# SCH_MUSICA.net
KiCad netlist of a schematic drawn in EasyEDA
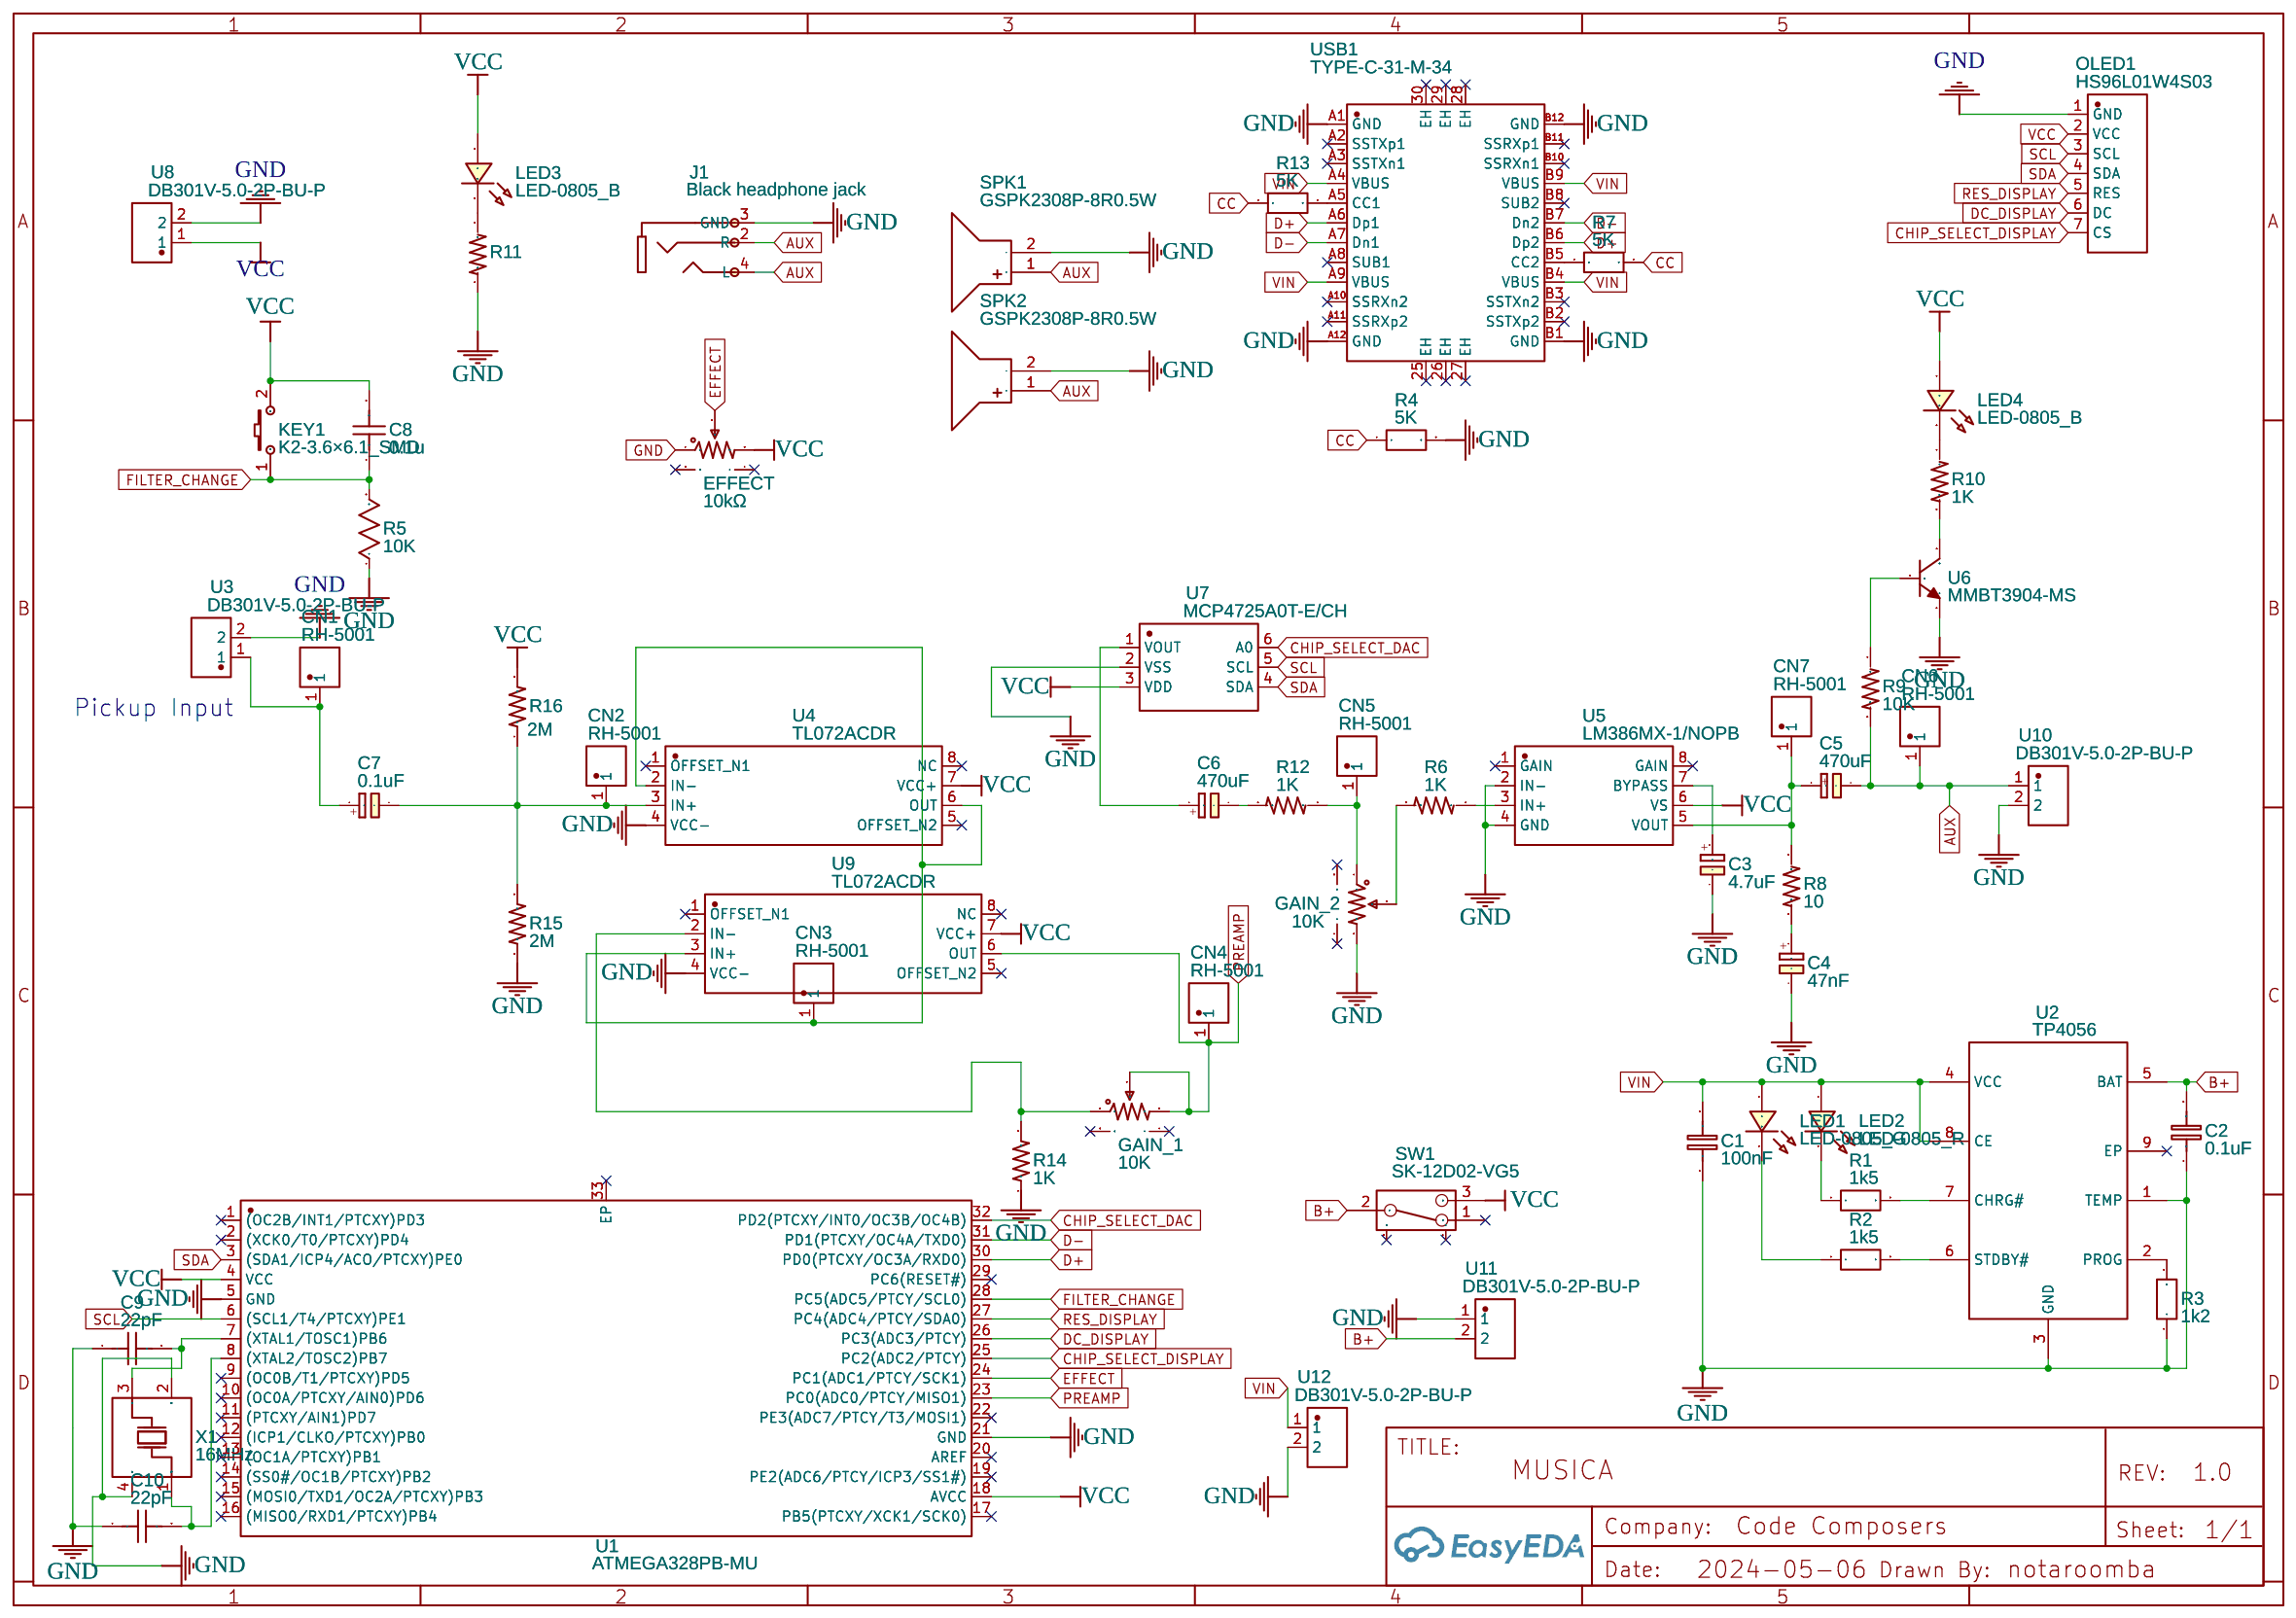
[diagram p0: schematic sheet]

(export (version "E")
  (design (tool "Eeschema 10.0.6"))
  (components
    (comp (ref "C1") (value "100nF") (libsource (lib "") (part "C_0603_EU")))
    (comp (ref "C2") (value "0.1uF") (libsource (lib "") (part "C_0603_EU")))
    (comp (ref "C3") (value "4.7uF") (libsource (lib "") (part "CAPACITOR_POL_S_1")))
    (comp (ref "C4") (value "47nF") (libsource (lib "") (part "CAPACITOR_POL_S_1")))
    (comp (ref "C5") (value "470uF") (libsource (lib "") (part "CAPACITOR_POL_S_2")))
    (comp (ref "C6") (value "470uF") (libsource (lib "") (part "CAPACITOR_POL_S")))
    (comp (ref "C7") (value "0.1uF") (libsource (lib "") (part "CAPACITOR_POL_S")))
    (comp (ref "C8") (value "0.1u") (libsource (lib "") (part "C_0603_US_1")))
    (comp (ref "C9") (value "22pF") (libsource (lib "") (part "C_0603_US")))
    (comp (ref "C10") (value "22pF") (libsource (lib "") (part "C_0603_US")))
    (comp (ref "CN1")
      (value "RH-5001")
      (fields (field (name "Manufacturer") "荣和"))
      (libsource (lib "") (part "RH-5001"))
    )
    (comp (ref "CN2")
      (value "RH-5001")
      (fields (field (name "Manufacturer") "荣和"))
      (libsource (lib "") (part "RH-5001"))
    )
    (comp (ref "CN3")
      (value "RH-5001")
      (fields (field (name "Manufacturer") "荣和"))
      (libsource (lib "") (part "RH-5001"))
    )
    (comp (ref "CN4")
      (value "RH-5001")
      (fields (field (name "Manufacturer") "荣和"))
      (libsource (lib "") (part "RH-5001"))
    )
    (comp (ref "CN5")
      (value "RH-5001")
      (fields (field (name "Manufacturer") "荣和"))
      (libsource (lib "") (part "RH-5001"))
    )
    (comp (ref "CN6")
      (value "RH-5001")
      (fields (field (name "Manufacturer") "荣和"))
      (libsource (lib "") (part "RH-5001"))
    )
    (comp (ref "CN7")
      (value "RH-5001")
      (fields (field (name "Manufacturer") "荣和"))
      (libsource (lib "") (part "RH-5001"))
    )
    (comp (ref "EFFECT")
      (value "10kΩ")
      (fields
        (field (name "Manufacturer Part") "RK09L114001T")
        (field (name "Manufacturer") "ALPSALPINE(阿尔卑斯阿尔派)")
      )
      (libsource (lib "") (part "RK09L114001T_2"))
    )
    (comp (ref "GAIN_1")
      (value "10K")
      (fields
        (field (name "Manufacturer Part") "RK09L114001T")
        (field (name "Manufacturer") "ALPSALPINE(阿尔卑斯阿尔派)")
      )
      (libsource (lib "") (part "RK09L114001T_1"))
    )
    (comp (ref "GAIN_2")
      (value "10K")
      (fields
        (field (name "Manufacturer Part") "RK09L114001T")
        (field (name "Manufacturer") "ALPSALPINE(阿尔卑斯阿尔派)")
      )
      (libsource (lib "") (part "RK09L114001T"))
    )
    (comp (ref "J1")
      (value "Black headphone jack")
      (fields (field (name "Manufacturer Part") "320B直插") (field (name "Manufacturer") "BOOMELE(博穆精密)"))
      (libsource (lib "") (part "Black headphone jack"))
    )
    (comp (ref "KEY1")
      (value "K2-3.6×6.1_SMD")
      (fields (field (name "Manufacturer Part") "K2-1107ST-A4SW-06"))
      (libsource (lib "") (part "K2-3.6×6.1_SMD"))
    )
    (comp (ref "LED1")
      (value "LED-0805_G")
      (fields (field (name "Manufacturer Part") "NCD0805G1") (field (name "Manufacturer") "国星光电"))
      (libsource (lib "") (part "LED-0805_G"))
    )
    (comp (ref "LED2")
      (value "LED-0805_R")
      (fields
        (field (name "Manufacturer Part") "17-21SURC/S530-A3/TR8")
        (field (name "Manufacturer") "EVERLIGHT(台湾亿光)")
      )
      (libsource (lib "") (part "LED-0805_R"))
    )
    (comp (ref "LED3")
      (value "LED-0805_B")
      (fields (field (name "Manufacturer Part") "D-B080508B1-KS2") (field (name "Manufacturer") "方舟 ARKLED"))
      (libsource (lib "") (part "LED-0805_B"))
    )
    (comp (ref "LED4")
      (value "LED-0805_B")
      (fields (field (name "Manufacturer Part") "D-B080508B1-KS2") (field (name "Manufacturer") "方舟 ARKLED"))
      (libsource (lib "") (part "LED-0805_B"))
    )
    (comp (ref "OLED1")
      (value "HS96L01W4S03")
      (fields (field (name "Manufacturer") "HS(汉昇)"))
      (libsource (lib "") (part "HS96L01W4S03"))
    )
    (comp (ref "R1") (value "1k5") (libsource (lib "") (part "R_0603_EU")))
    (comp (ref "R2") (value "1k5") (libsource (lib "") (part "R_0603_EU")))
    (comp (ref "R3") (value "1k2") (libsource (lib "") (part "R_0603_EU_1")))
    (comp (ref "R4") (value "5K") (libsource (lib "") (part "R_0603_EU")))
    (comp (ref "R5") (value "10K") (libsource (lib "") (part "R_0603_US")))
    (comp (ref "R6") (value "1K") (libsource (lib "") (part "RESISTOR0805-RES_2")))
    (comp (ref "R7") (value "5K") (libsource (lib "") (part "R_0603_EU")))
    (comp (ref "R8") (value "10") (libsource (lib "") (part "RESISTOR0805-RES_1")))
    (comp (ref "R9") (value "10K") (libsource (lib "") (part "RESISTOR0805-RES_1")))
    (comp (ref "R10") (value "1K") (libsource (lib "") (part "RESISTOR0805-RES_1")))
    (comp (ref "R11") (value "1K") (libsource (lib "") (part "RESISTOR0805-RES_1")))
    (comp (ref "R12") (value "1K") (libsource (lib "") (part "RESISTOR0805-RES_2")))
    (comp (ref "R13") (value "5K") (libsource (lib "") (part "R_0603_EU")))
    (comp (ref "R14") (value "1K") (libsource (lib "") (part "RESISTOR0805-RES")))
    (comp (ref "R15") (value "2M") (libsource (lib "") (part "RESISTOR0805-RES")))
    (comp (ref "R16") (value "2M") (libsource (lib "") (part "RESISTOR0805-RES")))
    (comp (ref "SPK1")
      (value "GSPK2308P-8R0.5W")
      (fields (field (name "Manufacturer") "INGHAi(赢海)"))
      (libsource (lib "") (part "GSPK2308P-8R0.5W"))
    )
    (comp (ref "SPK2")
      (value "GSPK2308P-8R0.5W")
      (fields (field (name "Manufacturer") "INGHAi(赢海)"))
      (libsource (lib "") (part "GSPK2308P-8R0.5W"))
    )
    (comp (ref "SW1")
      (value "SK-12D02-VG5")
      (fields (field (name "Manufacturer") "Rectangular Connectors - Contacts"))
      (libsource (lib "") (part "SK-12D02-VG5"))
    )
    (comp (ref "U1")
      (value "ATMEGA328PB-MU")
      (fields (field (name "Manufacturer") "MICROCHIP(美国微芯)"))
      (libsource (lib "") (part "ATMEGA328PB-MU"))
    )
    (comp (ref "U2")
      (value "TP4056")
      (fields
        (field (name "Manufacturer Part") "TP4056-42-ESOP8")
        (field (name "Manufacturer") "TOPPOWER(南京拓微)")
      )
      (libsource (lib "") (part "TP4056"))
    )
    (comp (ref "U3")
      (value "DB301V-5.0-2P-BU-P")
      (fields (field (name "Manufacturer") "DORABO(地博电气)"))
      (libsource (lib "") (part "DB301V-5.0-2P-BU-P"))
    )
    (comp (ref "U4")
      (value "TL072ACDR")
      (fields (field (name "Manufacturer") "TI(德州仪器)"))
      (libsource (lib "") (part "TL072ACDR"))
    )
    (comp (ref "U5")
      (value "LM386MX-1/NOPB")
      (fields (field (name "Manufacturer") "TI(德州仪器)"))
      (libsource (lib "") (part "LM386MX-1/NOPB"))
    )
    (comp (ref "U6")
      (value "MMBT3904-MS")
      (fields (field (name "Manufacturer") "MSKSEMI(美森科)"))
      (libsource (lib "") (part "MMBT3904-MS"))
    )
    (comp (ref "U7")
      (value "MCP4725A0T-E/CH")
      (fields (field (name "Manufacturer") "MICROCHIP(美国微芯)"))
      (libsource (lib "") (part "MCP4725A0T-E/CH"))
    )
    (comp (ref "U8")
      (value "DB301V-5.0-2P-BU-P")
      (fields (field (name "Manufacturer") "DORABO(地博电气)"))
      (libsource (lib "") (part "DB301V-5.0-2P-BU-P"))
    )
    (comp (ref "U9")
      (value "TL072ACDR")
      (fields (field (name "Manufacturer") "TI(德州仪器)"))
      (libsource (lib "") (part "TL072ACDR"))
    )
    (comp (ref "U10")
      (value "DB301V-5.0-2P-BU-P")
      (fields (field (name "Manufacturer") "DORABO(地博电气)"))
      (libsource (lib "") (part "DB301V-5.0-2P-BU-P_1"))
    )
    (comp (ref "U11")
      (value "DB301V-5.0-2P-BU-P")
      (fields (field (name "Manufacturer") "DORABO(地博电气)"))
      (libsource (lib "") (part "DB301V-5.0-2P-BU-P_1"))
    )
    (comp (ref "U12")
      (value "DB301V-5.0-2P-BU-P")
      (fields (field (name "Manufacturer") "DORABO(地博电气)"))
      (libsource (lib "") (part "DB301V-5.0-2P-BU-P_1"))
    )
    (comp (ref "USB1")
      (value "TYPE-C-31-M-34")
      (fields (field (name "Manufacturer") "韩国韩荣"))
      (libsource (lib "") (part "TYPE-C-31-M-34"))
    )
    (comp (ref "X1")
      (value "16MHz")
      (fields (field (name "Manufacturer Part") "X322516MLB4SI") (field (name "Manufacturer") "YXC(扬兴晶振)"))
      (libsource (lib "") (part "X322516MLB4SI"))
    )
  )
  (nets
    (net (code "1") (name "AUX") (class "Default")
      (node (ref "C5") (pin "-") (pinfunction "-_-") (pintype "unspecified"))
      (node (ref "CN6") (pin "1") (pinfunction "1_1") (pintype "unspecified"))
      (node (ref "J1") (pin "2") (pinfunction "R_2") (pintype "input"))
      (node (ref "J1") (pin "4") (pinfunction "L_4") (pintype "input"))
      (node (ref "R9") (pin "2") (pinfunction "2_2") (pintype "bidirectional"))
      (node (ref "SPK1") (pin "1") (pinfunction "+_1") (pintype "unspecified"))
      (node (ref "SPK2") (pin "1") (pinfunction "+_1") (pintype "unspecified"))
      (node (ref "U10") (pin "1") (pinfunction "1_1") (pintype "unspecified"))
    )
    (net (code "2") (name "B+") (class "Default")
      (node (ref "C2") (pin "2") (pinfunction "2_2") (pintype "unspecified"))
      (node (ref "SW1") (pin "2") (pinfunction "2_2") (pintype "unspecified"))
      (node (ref "U11") (pin "2") (pinfunction "2_2") (pintype "unspecified"))
      (node (ref "U2") (pin "5") (pinfunction "BAT_5") (pintype "unspecified"))
    )
    (net (code "3") (name "CC") (class "Default")
      (node (ref "R13") (pin "1") (pinfunction "1_1") (pintype "unspecified"))
      (node (ref "R4") (pin "1") (pinfunction "1_1") (pintype "unspecified"))
      (node (ref "R7") (pin "2") (pinfunction "2_2") (pintype "unspecified"))
    )
    (net (code "4") (name "CHIP_SELECT_DAC") (class "Default")
      (node (ref "U1") (pin "32") (pinfunction "PD2(PTCXY/INT0/OC3B/OC4B)_32") (pintype "unspecified"))
      (node (ref "U7") (pin "6") (pinfunction "A0_6") (pintype "unspecified"))
    )
    (net (code "5") (name "CHIP_SELECT_DISPLAY") (class "Default")
      (node (ref "OLED1") (pin "7") (pinfunction "CS_7") (pintype "unspecified"))
      (node (ref "U1") (pin "25") (pinfunction "PC2(ADC2/PTCY)_25") (pintype "unspecified"))
    )
    (net (code "6") (name "D+") (class "Default")
      (node (ref "U1") (pin "30") (pinfunction "PD0(PTCXY/OC3A/RXD0)_30") (pintype "unspecified"))
      (node (ref "USB1") (pin "A6") (pinfunction "Dp1_A6") (pintype "unspecified"))
      (node (ref "USB1") (pin "B6") (pinfunction "Dp2_B6") (pintype "unspecified"))
    )
    (net (code "7") (name "D-") (class "Default")
      (node (ref "U1") (pin "31") (pinfunction "PD1(PTCXY/OC4A/TXD0)_31") (pintype "unspecified"))
      (node (ref "USB1") (pin "A7") (pinfunction "Dn1_A7") (pintype "unspecified"))
      (node (ref "USB1") (pin "B7") (pinfunction "Dn2_B7") (pintype "unspecified"))
    )
    (net (code "8") (name "DC_DISPLAY") (class "Default")
      (node (ref "OLED1") (pin "6") (pinfunction "DC_6") (pintype "unspecified"))
      (node (ref "U1") (pin "26") (pinfunction "PC3(ADC3/PTCY)_26") (pintype "unspecified"))
    )
    (net (code "9") (name "EFFECT") (class "Default")
      (node (ref "EFFECT") (pin "2") (pinfunction "2_2") (pintype "unspecified"))
      (node (ref "U1") (pin "24") (pinfunction "PC1(ADC1/PTCY/SCK1)_24") (pintype "unspecified"))
    )
    (net (code "10") (name "FILTER_CHANGE") (class "Default")
      (node (ref "C8") (pin "1") (pinfunction "1_1") (pintype "unspecified"))
      (node (ref "KEY1") (pin "1") (pinfunction "1_1") (pintype "unspecified"))
      (node (ref "R5") (pin "2") (pinfunction "2_2") (pintype "unspecified"))
      (node (ref "U1") (pin "28") (pinfunction "PC5(ADC5/PTCY/SCL0)_28") (pintype "unspecified"))
    )
    (net (code "11") (name "GND") (class "Default")
      (node (ref "C1") (pin "1") (pinfunction "1_1") (pintype "unspecified"))
      (node (ref "C10") (pin "1") (pinfunction "1_1") (pintype "unspecified"))
      (node (ref "C2") (pin "1") (pinfunction "1_1") (pintype "unspecified"))
      (node (ref "C3") (pin "-") (pinfunction "-_-") (pintype "unspecified"))
      (node (ref "C4") (pin "-") (pinfunction "-_-") (pintype "unspecified"))
      (node (ref "C9") (pin "1") (pinfunction "1_1") (pintype "unspecified"))
      (node (ref "EFFECT") (pin "1") (pinfunction "1_1") (pintype "unspecified"))
      (node (ref "GAIN_2") (pin "3") (pinfunction "3_3") (pintype "unspecified"))
      (node (ref "J1") (pin "3") (pinfunction "GND_3") (pintype "input"))
      (node (ref "OLED1") (pin "1") (pinfunction "GND_1") (pintype "unspecified"))
      (node (ref "R11") (pin "2") (pinfunction "2_2") (pintype "bidirectional"))
      (node (ref "R14") (pin "1") (pinfunction "1_1") (pintype "bidirectional"))
      (node (ref "R15") (pin "1") (pinfunction "1_1") (pintype "bidirectional"))
      (node (ref "R3") (pin "1") (pinfunction "1_1") (pintype "unspecified"))
      (node (ref "R4") (pin "2") (pinfunction "2_2") (pintype "unspecified"))
      (node (ref "R5") (pin "1") (pinfunction "1_1") (pintype "unspecified"))
      (node (ref "SPK1") (pin "2") (pinfunction "-_2") (pintype "unspecified"))
      (node (ref "SPK2") (pin "2") (pinfunction "-_2") (pintype "unspecified"))
      (node (ref "U1") (pin "21") (pinfunction "GND_21") (pintype "unspecified"))
      (node (ref "U1") (pin "5") (pinfunction "GND_5") (pintype "unspecified"))
      (node (ref "U10") (pin "2") (pinfunction "2_2") (pintype "unspecified"))
      (node (ref "U11") (pin "1") (pinfunction "1_1") (pintype "unspecified"))
      (node (ref "U12") (pin "2") (pinfunction "2_2") (pintype "unspecified"))
      (node (ref "U2") (pin "1") (pinfunction "TEMP_1") (pintype "unspecified"))
      (node (ref "U2") (pin "3") (pinfunction "GND_3") (pintype "unspecified"))
      (node (ref "U3") (pin "2") (pinfunction "2_2") (pintype "unspecified"))
      (node (ref "U4") (pin "4") (pinfunction "VCC-_4") (pintype "unspecified"))
      (node (ref "U5") (pin "2") (pinfunction "IN-_2") (pintype "unspecified"))
      (node (ref "U5") (pin "4") (pinfunction "GND_4") (pintype "unspecified"))
      (node (ref "U6") (pin "2") (pinfunction "E_2") (pintype "input"))
      (node (ref "U7") (pin "2") (pinfunction "VSS_2") (pintype "unspecified"))
      (node (ref "U8") (pin "2") (pinfunction "2_2") (pintype "unspecified"))
      (node (ref "U9") (pin "4") (pinfunction "VCC-_4") (pintype "unspecified"))
      (node (ref "USB1") (pin "A1") (pinfunction "GND_A1") (pintype "unspecified"))
      (node (ref "USB1") (pin "A12") (pinfunction "GND_A12") (pintype "unspecified"))
      (node (ref "USB1") (pin "B1") (pinfunction "GND_B1") (pintype "unspecified"))
      (node (ref "USB1") (pin "B12") (pinfunction "GND_B12") (pintype "unspecified"))
      (node (ref "X1") (pin "2") (pinfunction "GND_2") (pintype "unspecified"))
      (node (ref "X1") (pin "4") (pinfunction "GND_4") (pintype "unspecified"))
    )
    (net (code "12") (name "Net-(C4-Pad+)") (class "Default")
      (node (ref "C4") (pin "+") (pinfunction "+_+") (pintype "unspecified"))
      (node (ref "R8") (pin "2") (pinfunction "2_2") (pintype "bidirectional"))
    )
    (net (code "13") (name "Net-(C6-Pad-)") (class "Default")
      (node (ref "C6") (pin "-") (pinfunction "-_-") (pintype "unspecified"))
      (node (ref "R12") (pin "2") (pinfunction "2_2") (pintype "bidirectional"))
    )
    (net (code "14") (name "Net-(C7-Pad+)") (class "Default")
      (node (ref "C7") (pin "+") (pinfunction "+_+") (pintype "unspecified"))
      (node (ref "CN1") (pin "1") (pinfunction "1_1") (pintype "unspecified"))
      (node (ref "U3") (pin "1") (pinfunction "1_1") (pintype "unspecified"))
    )
    (net (code "15") (name "Net-(CN5-Pad1)") (class "Default")
      (node (ref "CN5") (pin "1") (pinfunction "1_1") (pintype "unspecified"))
      (node (ref "GAIN_2") (pin "1") (pinfunction "1_1") (pintype "unspecified"))
      (node (ref "R12") (pin "1") (pinfunction "1_1") (pintype "bidirectional"))
    )
    (net (code "16") (name "Net-(GAIN_2-Pad2)") (class "Default")
      (node (ref "GAIN_2") (pin "2") (pinfunction "2_2") (pintype "unspecified"))
      (node (ref "R6") (pin "2") (pinfunction "2_2") (pintype "bidirectional"))
    )
    (net (code "17") (name "Net-(LED1-Pad2)") (class "Default")
      (node (ref "LED1") (pin "2") (pinfunction "2_2") (pintype "unspecified"))
      (node (ref "R2") (pin "1") (pinfunction "1_1") (pintype "unspecified"))
    )
    (net (code "18") (name "Net-(LED2-Pad2)") (class "Default")
      (node (ref "LED2") (pin "2") (pinfunction "2_2") (pintype "unspecified"))
      (node (ref "R1") (pin "1") (pinfunction "1_1") (pintype "unspecified"))
    )
    (net (code "19") (name "Net-(LED3-Pad2)") (class "Default")
      (node (ref "LED3") (pin "2") (pinfunction "2_2") (pintype "unspecified"))
      (node (ref "R11") (pin "1") (pinfunction "1_1") (pintype "bidirectional"))
    )
    (net (code "20") (name "Net-(LED4-Pad2)") (class "Default")
      (node (ref "LED4") (pin "2") (pinfunction "2_2") (pintype "unspecified"))
      (node (ref "R10") (pin "1") (pinfunction "1_1") (pintype "bidirectional"))
    )
    (net (code "21") (name "Net-(U1-(XTAL1{slash}TOSC1)PB6)") (class "Default")
      (node (ref "C9") (pin "2") (pinfunction "2_2") (pintype "unspecified"))
      (node (ref "U1") (pin "7") (pinfunction "(XTAL1/TOSC1)PB6_7") (pintype "unspecified"))
      (node (ref "X1") (pin "3") (pinfunction "OSC2_3") (pintype "unspecified"))
    )
    (net (code "22") (name "Net-(U1-(XTAL2{slash}TOSC2)PB7)") (class "Default")
      (node (ref "C10") (pin "2") (pinfunction "2_2") (pintype "unspecified"))
      (node (ref "U1") (pin "8") (pinfunction "(XTAL2/TOSC2)PB7_8") (pintype "unspecified"))
      (node (ref "X1") (pin "1") (pinfunction "OSC1_1") (pintype "unspecified"))
    )
    (net (code "23") (name "Net-(U2-CHRG#)") (class "Default")
      (node (ref "R1") (pin "2") (pinfunction "2_2") (pintype "unspecified"))
      (node (ref "U2") (pin "7") (pinfunction "CHRG#_7") (pintype "unspecified"))
    )
    (net (code "24") (name "Net-(U2-PROG)") (class "Default")
      (node (ref "R3") (pin "2") (pinfunction "2_2") (pintype "unspecified"))
      (node (ref "U2") (pin "2") (pinfunction "PROG_2") (pintype "unspecified"))
    )
    (net (code "25") (name "Net-(U2-STDBY#)") (class "Default")
      (node (ref "R2") (pin "2") (pinfunction "2_2") (pintype "unspecified"))
      (node (ref "U2") (pin "6") (pinfunction "STDBY#_6") (pintype "unspecified"))
    )
    (net (code "26") (name "Net-(U4-IN+)") (class "Default")
      (node (ref "C7") (pin "-") (pinfunction "-_-") (pintype "unspecified"))
      (node (ref "CN2") (pin "1") (pinfunction "1_1") (pintype "unspecified"))
      (node (ref "R15") (pin "2") (pinfunction "2_2") (pintype "bidirectional"))
      (node (ref "R16") (pin "1") (pinfunction "1_1") (pintype "bidirectional"))
      (node (ref "U4") (pin "3") (pinfunction "IN+_3") (pintype "unspecified"))
    )
    (net (code "27") (name "Net-(U4-IN-)") (class "Default")
      (node (ref "CN3") (pin "1") (pinfunction "1_1") (pintype "unspecified"))
      (node (ref "U4") (pin "2") (pinfunction "IN-_2") (pintype "unspecified"))
      (node (ref "U4") (pin "6") (pinfunction "OUT_6") (pintype "unspecified"))
      (node (ref "U9") (pin "3") (pinfunction "IN+_3") (pintype "unspecified"))
    )
    (net (code "28") (name "Net-(U5-BYPASS)") (class "Default")
      (node (ref "C3") (pin "+") (pinfunction "+_+") (pintype "unspecified"))
      (node (ref "U5") (pin "7") (pinfunction "BYPASS_7") (pintype "unspecified"))
    )
    (net (code "29") (name "Net-(U5-IN+)") (class "Default")
      (node (ref "R6") (pin "1") (pinfunction "1_1") (pintype "bidirectional"))
      (node (ref "U5") (pin "3") (pinfunction "IN+_3") (pintype "unspecified"))
    )
    (net (code "30") (name "Net-(U5-VOUT)") (class "Default")
      (node (ref "C5") (pin "+") (pinfunction "+_+") (pintype "unspecified"))
      (node (ref "CN7") (pin "1") (pinfunction "1_1") (pintype "unspecified"))
      (node (ref "R8") (pin "1") (pinfunction "1_1") (pintype "bidirectional"))
      (node (ref "U5") (pin "5") (pinfunction "VOUT_5") (pintype "unspecified"))
    )
    (net (code "31") (name "Net-(U6-B)") (class "Default")
      (node (ref "R9") (pin "1") (pinfunction "1_1") (pintype "bidirectional"))
      (node (ref "U6") (pin "1") (pinfunction "B_1") (pintype "input"))
    )
    (net (code "32") (name "Net-(U6-C)") (class "Default")
      (node (ref "R10") (pin "2") (pinfunction "2_2") (pintype "bidirectional"))
      (node (ref "U6") (pin "3") (pinfunction "C_3") (pintype "input"))
    )
    (net (code "33") (name "Net-(U7-VOUT)") (class "Default")
      (node (ref "C6") (pin "+") (pinfunction "+_+") (pintype "unspecified"))
      (node (ref "U7") (pin "1") (pinfunction "VOUT_1") (pintype "unspecified"))
    )
    (net (code "34") (name "Net-(U9-IN-)") (class "Default")
      (node (ref "GAIN_1") (pin "1") (pinfunction "1_1") (pintype "unspecified"))
      (node (ref "R14") (pin "2") (pinfunction "2_2") (pintype "bidirectional"))
      (node (ref "U9") (pin "2") (pinfunction "IN-_2") (pintype "unspecified"))
    )
    (net (code "35") (name "Net-(USB1-CC1)") (class "Default")
      (node (ref "R13") (pin "2") (pinfunction "2_2") (pintype "unspecified"))
      (node (ref "USB1") (pin "A5") (pinfunction "CC1_A5") (pintype "unspecified"))
    )
    (net (code "36") (name "Net-(USB1-CC2)") (class "Default")
      (node (ref "R7") (pin "1") (pinfunction "1_1") (pintype "unspecified"))
      (node (ref "USB1") (pin "B5") (pinfunction "CC2_B5") (pintype "unspecified"))
    )
    (net (code "37") (name "PREAMP") (class "Default")
      (node (ref "CN4") (pin "1") (pinfunction "1_1") (pintype "unspecified"))
      (node (ref "GAIN_1") (pin "2") (pinfunction "2_2") (pintype "unspecified"))
      (node (ref "GAIN_1") (pin "3") (pinfunction "3_3") (pintype "unspecified"))
      (node (ref "U1") (pin "23") (pinfunction "PC0(ADC0/PTCY/MISO1)_23") (pintype "unspecified"))
      (node (ref "U9") (pin "6") (pinfunction "OUT_6") (pintype "unspecified"))
    )
    (net (code "38") (name "RES_DISPLAY") (class "Default")
      (node (ref "OLED1") (pin "5") (pinfunction "RES_5") (pintype "unspecified"))
      (node (ref "U1") (pin "27") (pinfunction "PC4(ADC4/PTCY/SDA0)_27") (pintype "unspecified"))
    )
    (net (code "39") (name "SCL") (class "Default")
      (node (ref "OLED1") (pin "3") (pinfunction "SCL_3") (pintype "unspecified"))
      (node (ref "U1") (pin "6") (pinfunction "(SCL1/T4/PTCXY)PE1_6") (pintype "unspecified"))
      (node (ref "U7") (pin "5") (pinfunction "SCL_5") (pintype "unspecified"))
    )
    (net (code "40") (name "SDA") (class "Default")
      (node (ref "OLED1") (pin "4") (pinfunction "SDA_4") (pintype "unspecified"))
      (node (ref "U1") (pin "3") (pinfunction "(SDA1/ICP4/ACO/PTCXY)PE0_3") (pintype "unspecified"))
      (node (ref "U7") (pin "4") (pinfunction "SDA_4") (pintype "unspecified"))
    )
    (net (code "41") (name "VCC") (class "Default")
      (node (ref "C8") (pin "2") (pinfunction "2_2") (pintype "unspecified"))
      (node (ref "EFFECT") (pin "3") (pinfunction "3_3") (pintype "unspecified"))
      (node (ref "KEY1") (pin "2") (pinfunction "2_2") (pintype "unspecified"))
      (node (ref "LED3") (pin "1") (pinfunction "1_1") (pintype "unspecified"))
      (node (ref "LED4") (pin "1") (pinfunction "1_1") (pintype "unspecified"))
      (node (ref "OLED1") (pin "2") (pinfunction "VCC_2") (pintype "unspecified"))
      (node (ref "R16") (pin "2") (pinfunction "2_2") (pintype "bidirectional"))
      (node (ref "SW1") (pin "3") (pinfunction "3_3") (pintype "unspecified"))
      (node (ref "U1") (pin "18") (pinfunction "AVCC_18") (pintype "unspecified"))
      (node (ref "U1") (pin "4") (pinfunction "VCC_4") (pintype "unspecified"))
      (node (ref "U4") (pin "7") (pinfunction "VCC+_7") (pintype "unspecified"))
      (node (ref "U5") (pin "6") (pinfunction "VS_6") (pintype "unspecified"))
      (node (ref "U7") (pin "3") (pinfunction "VDD_3") (pintype "unspecified"))
      (node (ref "U8") (pin "1") (pinfunction "1_1") (pintype "unspecified"))
      (node (ref "U9") (pin "7") (pinfunction "VCC+_7") (pintype "unspecified"))
    )
    (net (code "42") (name "VIN") (class "Default")
      (node (ref "C1") (pin "2") (pinfunction "2_2") (pintype "unspecified"))
      (node (ref "LED1") (pin "1") (pinfunction "1_1") (pintype "unspecified"))
      (node (ref "LED2") (pin "1") (pinfunction "1_1") (pintype "unspecified"))
      (node (ref "U12") (pin "1") (pinfunction "1_1") (pintype "unspecified"))
      (node (ref "U2") (pin "4") (pinfunction "VCC_4") (pintype "unspecified"))
      (node (ref "U2") (pin "8") (pinfunction "CE_8") (pintype "unspecified"))
      (node (ref "USB1") (pin "A4") (pinfunction "VBUS_A4") (pintype "unspecified"))
      (node (ref "USB1") (pin "A9") (pinfunction "VBUS_A9") (pintype "unspecified"))
      (node (ref "USB1") (pin "B4") (pinfunction "VBUS_B4") (pintype "unspecified"))
      (node (ref "USB1") (pin "B9") (pinfunction "VBUS_B9") (pintype "unspecified"))
    )
    (net (code "43") (name "unconnected-(EFFECT-Pad4)") (class "Default")
      (node (ref "EFFECT") (pin "4") (pinfunction "4_4") (pintype "unspecified+no_connect"))
    )
    (net (code "44") (name "unconnected-(EFFECT-Pad5)") (class "Default")
      (node (ref "EFFECT") (pin "5") (pinfunction "5_5") (pintype "unspecified+no_connect"))
    )
    (net (code "45") (name "unconnected-(GAIN_1-Pad4)") (class "Default")
      (node (ref "GAIN_1") (pin "4") (pinfunction "4_4") (pintype "unspecified+no_connect"))
    )
    (net (code "46") (name "unconnected-(GAIN_1-Pad5)") (class "Default")
      (node (ref "GAIN_1") (pin "5") (pinfunction "5_5") (pintype "unspecified+no_connect"))
    )
    (net (code "47") (name "unconnected-(GAIN_2-Pad4)") (class "Default")
      (node (ref "GAIN_2") (pin "4") (pinfunction "4_4") (pintype "unspecified+no_connect"))
    )
    (net (code "48") (name "unconnected-(GAIN_2-Pad5)") (class "Default")
      (node (ref "GAIN_2") (pin "5") (pinfunction "5_5") (pintype "unspecified+no_connect"))
    )
    (net (code "49") (name "unconnected-(SW1-Pad1)") (class "Default")
      (node (ref "SW1") (pin "1") (pinfunction "1_1") (pintype "unspecified+no_connect"))
    )
    (net (code "50") (name "unconnected-(SW1-Pad4)") (class "Default")
      (node (ref "SW1") (pin "4") (pinfunction "4_4") (pintype "unspecified+no_connect"))
    )
    (net (code "51") (name "unconnected-(SW1-Pad5)") (class "Default")
      (node (ref "SW1") (pin "5") (pinfunction "5_5") (pintype "unspecified+no_connect"))
    )
    (net (code "52") (name "unconnected-(U1-(ICP1{slash}CLKO{slash}PTCXY)PB0-Pad12)") (class "Default")
      (node (ref "U1") (pin "12") (pinfunction "(ICP1/CLKO/PTCXY)PB0_12") (pintype "unspecified+no_connect"))
    )
    (net (code "53") (name "unconnected-(U1-(MISO0{slash}RXD1{slash}PTCXY)PB4-Pad16)") (class "Default")
      (node (ref "U1") (pin "16") (pinfunction "(MISO0/RXD1/PTCXY)PB4_16") (pintype "unspecified+no_connect"))
    )
    (net (code "54") (name "unconnected-(U1-(MOSI0{slash}TXD1{slash}OC2A{slash}PTCXY)PB3-Pad15)") (class "Default")
      (node (ref "U1") (pin "15") (pinfunction "(MOSI0/TXD1/OC2A/PTCXY)PB3_15") (pintype "unspecified+no_connect"))
    )
    (net (code "55") (name "unconnected-(U1-(OC0A{slash}PTCXY{slash}AIN0)PD6-Pad10)") (class "Default")
      (node (ref "U1") (pin "10") (pinfunction "(OC0A/PTCXY/AIN0)PD6_10") (pintype "unspecified+no_connect"))
    )
    (net (code "56") (name "unconnected-(U1-(OC0B{slash}T1{slash}PTCXY)PD5-Pad9)") (class "Default")
      (node (ref "U1") (pin "9") (pinfunction "(OC0B/T1/PTCXY)PD5_9") (pintype "unspecified+no_connect"))
    )
    (net (code "57") (name "unconnected-(U1-(OC1A{slash}PTCXY)PB1-Pad13)") (class "Default")
      (node (ref "U1") (pin "13") (pinfunction "(OC1A/PTCXY)PB1_13") (pintype "unspecified+no_connect"))
    )
    (net (code "58") (name "unconnected-(U1-(OC2B{slash}INT1{slash}PTCXY)PD3-Pad1)") (class "Default")
      (node (ref "U1") (pin "1") (pinfunction "(OC2B/INT1/PTCXY)PD3_1") (pintype "unspecified+no_connect"))
    )
    (net (code "59") (name "unconnected-(U1-(PTCXY{slash}AIN1)PD7-Pad11)") (class "Default")
      (node (ref "U1") (pin "11") (pinfunction "(PTCXY/AIN1)PD7_11") (pintype "unspecified+no_connect"))
    )
    (net (code "60") (name "unconnected-(U1-(SS0#{slash}OC1B{slash}PTCXY)PB2-Pad14)") (class "Default")
      (node (ref "U1") (pin "14") (pinfunction "(SS0#/OC1B/PTCXY)PB2_14") (pintype "unspecified+no_connect"))
    )
    (net (code "61") (name "unconnected-(U1-(XCK0{slash}T0{slash}PTCXY)PD4-Pad2)") (class "Default")
      (node (ref "U1") (pin "2") (pinfunction "(XCK0/T0/PTCXY)PD4_2") (pintype "unspecified+no_connect"))
    )
    (net (code "62") (name "unconnected-(U1-AREF-Pad20)") (class "Default")
      (node (ref "U1") (pin "20") (pinfunction "AREF_20") (pintype "unspecified+no_connect"))
    )
    (net (code "63") (name "unconnected-(U1-EP-Pad33)") (class "Default")
      (node (ref "U1") (pin "33") (pinfunction "EP_33") (pintype "unspecified+no_connect"))
    )
    (net (code "64") (name "unconnected-(U1-PB5(PTCXY{slash}XCK1{slash}SCK0)-Pad17)") (class "Default")
      (node (ref "U1") (pin "17") (pinfunction "PB5(PTCXY/XCK1/SCK0)_17") (pintype "unspecified+no_connect"))
    )
    (net (code "65") (name "unconnected-(U1-PC6(RESET#)-Pad29)") (class "Default")
      (node (ref "U1") (pin "29") (pinfunction "PC6(RESET#)_29") (pintype "unspecified+no_connect"))
    )
    (net (code "66") (name "unconnected-(U1-PE2(ADC6{slash}PTCY{slash}ICP3{slash}SS1#)-Pad19)") (class "Default")
      (node (ref "U1") (pin "19") (pinfunction "PE2(ADC6/PTCY/ICP3/SS1#)_19") (pintype "unspecified+no_connect"))
    )
    (net (code "67") (name "unconnected-(U1-PE3(ADC7{slash}PTCY{slash}T3{slash}MOSI1)-Pad22)") (class "Default")
      (node (ref "U1") (pin "22") (pinfunction "PE3(ADC7/PTCY/T3/MOSI1)_22") (pintype "unspecified+no_connect"))
    )
    (net (code "68") (name "unconnected-(U2-EP-Pad9)") (class "Default")
      (node (ref "U2") (pin "9") (pinfunction "EP_9") (pintype "unspecified+no_connect"))
    )
    (net (code "69") (name "unconnected-(U4-NC-Pad8)") (class "Default")
      (node (ref "U4") (pin "8") (pinfunction "NC_8") (pintype "unspecified+no_connect"))
    )
    (net (code "70") (name "unconnected-(U4-OFFSET_N1-Pad1)") (class "Default")
      (node (ref "U4") (pin "1") (pinfunction "OFFSET_N1_1") (pintype "unspecified+no_connect"))
    )
    (net (code "71") (name "unconnected-(U4-OFFSET_N2-Pad5)") (class "Default")
      (node (ref "U4") (pin "5") (pinfunction "OFFSET_N2_5") (pintype "unspecified+no_connect"))
    )
    (net (code "72") (name "unconnected-(U5-GAIN-Pad1)") (class "Default")
      (node (ref "U5") (pin "1") (pinfunction "GAIN_1") (pintype "unspecified+no_connect"))
    )
    (net (code "73") (name "unconnected-(U5-GAIN-Pad8)") (class "Default")
      (node (ref "U5") (pin "8") (pinfunction "GAIN_8") (pintype "unspecified+no_connect"))
    )
    (net (code "74") (name "unconnected-(U9-NC-Pad8)") (class "Default")
      (node (ref "U9") (pin "8") (pinfunction "NC_8") (pintype "unspecified+no_connect"))
    )
    (net (code "75") (name "unconnected-(U9-OFFSET_N1-Pad1)") (class "Default")
      (node (ref "U9") (pin "1") (pinfunction "OFFSET_N1_1") (pintype "unspecified+no_connect"))
    )
    (net (code "76") (name "unconnected-(U9-OFFSET_N2-Pad5)") (class "Default")
      (node (ref "U9") (pin "5") (pinfunction "OFFSET_N2_5") (pintype "unspecified+no_connect"))
    )
    (net (code "77") (name "unconnected-(USB1-EH-Pad25)") (class "Default")
      (node (ref "USB1") (pin "25") (pinfunction "EH_25") (pintype "unspecified+no_connect"))
    )
    (net (code "78") (name "unconnected-(USB1-EH-Pad26)") (class "Default")
      (node (ref "USB1") (pin "26") (pinfunction "EH_26") (pintype "unspecified+no_connect"))
    )
    (net (code "79") (name "unconnected-(USB1-EH-Pad27)") (class "Default")
      (node (ref "USB1") (pin "27") (pinfunction "EH_27") (pintype "unspecified+no_connect"))
    )
    (net (code "80") (name "unconnected-(USB1-EH-Pad28)") (class "Default")
      (node (ref "USB1") (pin "28") (pinfunction "EH_28") (pintype "unspecified+no_connect"))
    )
    (net (code "81") (name "unconnected-(USB1-EH-Pad29)") (class "Default")
      (node (ref "USB1") (pin "29") (pinfunction "EH_29") (pintype "unspecified+no_connect"))
    )
    (net (code "82") (name "unconnected-(USB1-EH-Pad30)") (class "Default")
      (node (ref "USB1") (pin "30") (pinfunction "EH_30") (pintype "unspecified+no_connect"))
    )
    (net (code "83") (name "unconnected-(USB1-SSRXn1-PadB10)") (class "Default")
      (node (ref "USB1") (pin "B10") (pinfunction "SSRXn1_B10") (pintype "unspecified+no_connect"))
    )
    (net (code "84") (name "unconnected-(USB1-SSRXn2-PadA10)") (class "Default")
      (node (ref "USB1") (pin "A10") (pinfunction "SSRXn2_A10") (pintype "unspecified+no_connect"))
    )
    (net (code "85") (name "unconnected-(USB1-SSRXp1-PadB11)") (class "Default")
      (node (ref "USB1") (pin "B11") (pinfunction "SSRXp1_B11") (pintype "unspecified+no_connect"))
    )
    (net (code "86") (name "unconnected-(USB1-SSRXp2-PadA11)") (class "Default")
      (node (ref "USB1") (pin "A11") (pinfunction "SSRXp2_A11") (pintype "unspecified+no_connect"))
    )
    (net (code "87") (name "unconnected-(USB1-SSTXn1-PadA3)") (class "Default")
      (node (ref "USB1") (pin "A3") (pinfunction "SSTXn1_A3") (pintype "unspecified+no_connect"))
    )
    (net (code "88") (name "unconnected-(USB1-SSTXn2-PadB3)") (class "Default")
      (node (ref "USB1") (pin "B3") (pinfunction "SSTXn2_B3") (pintype "unspecified+no_connect"))
    )
    (net (code "89") (name "unconnected-(USB1-SSTXp1-PadA2)") (class "Default")
      (node (ref "USB1") (pin "A2") (pinfunction "SSTXp1_A2") (pintype "unspecified+no_connect"))
    )
    (net (code "90") (name "unconnected-(USB1-SSTXp2-PadB2)") (class "Default")
      (node (ref "USB1") (pin "B2") (pinfunction "SSTXp2_B2") (pintype "unspecified+no_connect"))
    )
    (net (code "91") (name "unconnected-(USB1-SUB1-PadA8)") (class "Default")
      (node (ref "USB1") (pin "A8") (pinfunction "SUB1_A8") (pintype "unspecified+no_connect"))
    )
    (net (code "92") (name "unconnected-(USB1-SUB2-PadB8)") (class "Default")
      (node (ref "USB1") (pin "B8") (pinfunction "SUB2_B8") (pintype "unspecified+no_connect"))
    )
  )
)
